# lightfun.net
KiCad netlist of a schematic drawn in EAGLE
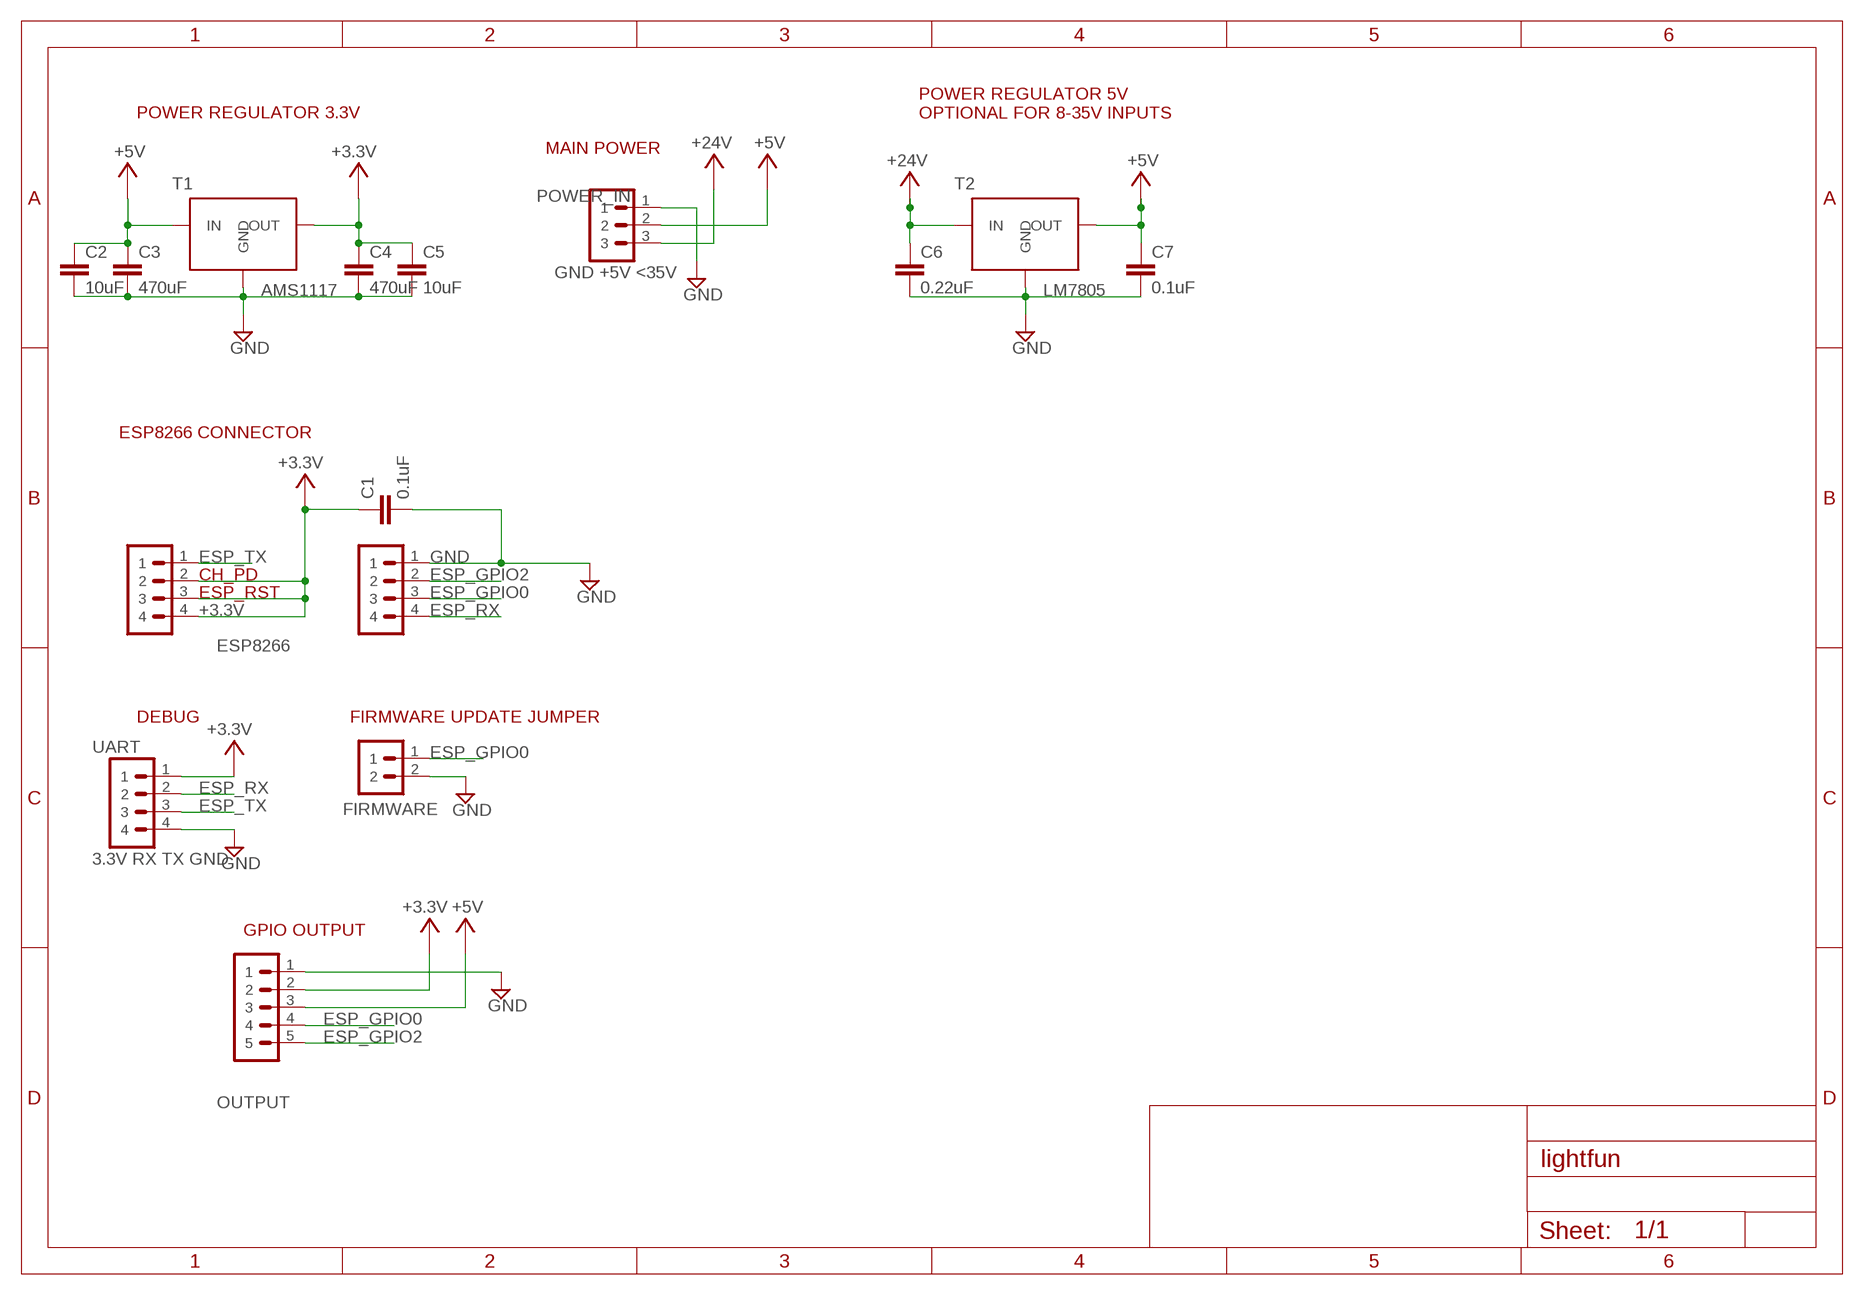
[diagram p0: schematic, sheet 1]

(export (version "E")
  (design (tool "Eeschema 10.0.6"))
  (components
    (comp (ref "C1")
      (value "0.1uF")
      (footprint "eagle-import:C2.5-2")
      (libsource (lib "eagle-import") (part "C2.5/2"))
    )
    (comp (ref "C2")
      (value "10uF")
      (footprint "eagle-import:C2.5-2")
      (libsource (lib "eagle-import") (part "C2.5/2"))
    )
    (comp (ref "C3")
      (value "470uF")
      (footprint "eagle-import:C2.5-2")
      (fields (field (name "MPN") "1C10Z5U104M050B"))
      (libsource (lib "eagle-import") (part "C2.5/2"))
    )
    (comp (ref "C4")
      (value "470uF")
      (footprint "eagle-import:C2.5-2")
      (fields (field (name "MPN") "FK18X5R0J106M"))
      (libsource (lib "eagle-import") (part "C2.5/2"))
    )
    (comp (ref "C5")
      (value "10uF")
      (footprint "eagle-import:C2.5-2")
      (libsource (lib "eagle-import") (part "C2.5/2"))
    )
    (comp (ref "C6")
      (value "0.22uF")
      (footprint "eagle-import:C2.5-2")
      (fields (field (name "MPN") "1C10Z5U104M050B"))
      (libsource (lib "eagle-import") (part "C2.5/2"))
    )
    (comp (ref "C7")
      (value "0.1uF")
      (footprint "eagle-import:C2.5-2")
      (fields (field (name "MPN") "FK18X5R0J106M"))
      (libsource (lib "eagle-import") (part "C2.5/2"))
    )
    (comp (ref "FIRMWARE")
      (value "FIRMWARE")
      (footprint "eagle-import:PIN-HEADER-2PIN")
      (libsource (lib "eagle-import") (part "PIN-HEADER-2PIN"))
    )
    (comp (ref "OUTPUT")
      (value "GND 3.3V 5V IO0 IO2")
      (footprint "eagle-import:PIN-HEADER-5PIN")
      (libsource (lib "eagle-import") (part "PIN-HEADER-5PIN"))
    )
    (comp (ref "P1")
      (value "ESP8266")
      (footprint "eagle-import:PIN-HEADER-4PIN")
      (libsource (lib "eagle-import") (part "PIN-HEADER-4PIN"))
    )
    (comp (ref "P2")
      (value "ESP8266 CONNECTOR")
      (footprint "eagle-import:PIN-HEADER-4PIN")
      (libsource (lib "eagle-import") (part "PIN-HEADER-4PIN"))
    )
    (comp (ref "POWER_IN")
      (value "GND +5V <35V")
      (footprint "eagle-import:PIN-HEADER-3PIN")
      (libsource (lib "eagle-import") (part "PIN-HEADER-3PIN"))
    )
    (comp (ref "T1")
      (value "AMS1117")
      (footprint "eagle-import:SOT-223")
      (fields (field (name "MPN") "LM2937ET-3.3"))
      (libsource (lib "eagle-import") (part "AMS1117"))
    )
    (comp (ref "T2")
      (value "LM7805")
      (footprint "eagle-import:TO-220")
      (fields (field (name "MPN") "LM2937ET-3.3"))
      (libsource (lib "eagle-import") (part "LM7805"))
    )
    (comp (ref "UART")
      (value "3.3V RX TX GND")
      (footprint "eagle-import:PIN-HEADER-4PIN")
      (libsource (lib "eagle-import") (part "PIN-HEADER-4PIN"))
    )
  )
  (nets
    (net (code "1") (name "+3.3V") (class "Default")
      (node (ref "C1") (pin "1") (pinfunction "1_1") (pintype "passive"))
      (node (ref "C4") (pin "1") (pinfunction "1_1") (pintype "passive"))
      (node (ref "C5") (pin "1") (pinfunction "1_1") (pintype "passive"))
      (node (ref "OUTPUT") (pin "2") (pinfunction "2_2") (pintype "passive"))
      (node (ref "P1") (pin "2") (pinfunction "2_2") (pintype "passive"))
      (node (ref "P1") (pin "3") (pinfunction "3_3") (pintype "passive"))
      (node (ref "P1") (pin "4") (pinfunction "4_4") (pintype "passive"))
      (node (ref "T1") (pin "2") (pinfunction "OUT_2") (pintype "power_in"))
      (node (ref "UART") (pin "1") (pinfunction "1_1") (pintype "passive"))
    )
    (net (code "2") (name "+5V") (class "Default")
      (node (ref "C2") (pin "1") (pinfunction "1_1") (pintype "passive"))
      (node (ref "C3") (pin "1") (pinfunction "1_1") (pintype "passive"))
      (node (ref "C7") (pin "1") (pinfunction "1_1") (pintype "passive"))
      (node (ref "OUTPUT") (pin "3") (pinfunction "3_3") (pintype "passive"))
      (node (ref "POWER_IN") (pin "2") (pinfunction "2_2") (pintype "passive"))
      (node (ref "T1") (pin "3") (pinfunction "IN_3") (pintype "power_in"))
      (node (ref "T2") (pin "OUTPUT") (pinfunction "OUT_OUTPUT") (pintype "power_in"))
    )
    (net (code "3") (name "+24V") (class "Default")
      (node (ref "C6") (pin "1") (pinfunction "1_1") (pintype "passive"))
      (node (ref "POWER_IN") (pin "3") (pinfunction "3_3") (pintype "passive"))
      (node (ref "T2") (pin "INPUT") (pinfunction "IN_INPUT") (pintype "power_in"))
    )
    (net (code "4") (name "/ESP_GPIO0") (class "Default")
      (node (ref "FIRMWARE") (pin "1") (pinfunction "1_1") (pintype "passive"))
      (node (ref "OUTPUT") (pin "4") (pinfunction "4_4") (pintype "passive"))
      (node (ref "P2") (pin "3") (pinfunction "3_3") (pintype "passive"))
    )
    (net (code "5") (name "/ESP_GPIO2") (class "Default")
      (node (ref "OUTPUT") (pin "5") (pinfunction "5_5") (pintype "passive"))
      (node (ref "P2") (pin "2") (pinfunction "2_2") (pintype "passive"))
    )
    (net (code "6") (name "/ESP_RX") (class "Default")
      (node (ref "P2") (pin "4") (pinfunction "4_4") (pintype "passive"))
      (node (ref "UART") (pin "2") (pinfunction "2_2") (pintype "passive"))
    )
    (net (code "7") (name "/ESP_TX") (class "Default")
      (node (ref "P1") (pin "1") (pinfunction "1_1") (pintype "passive"))
      (node (ref "UART") (pin "3") (pinfunction "3_3") (pintype "passive"))
    )
    (net (code "8") (name "GND") (class "Default")
      (node (ref "C1") (pin "2") (pinfunction "2_2") (pintype "passive"))
      (node (ref "C2") (pin "2") (pinfunction "2_2") (pintype "passive"))
      (node (ref "C3") (pin "2") (pinfunction "2_2") (pintype "passive"))
      (node (ref "C4") (pin "2") (pinfunction "2_2") (pintype "passive"))
      (node (ref "C5") (pin "2") (pinfunction "2_2") (pintype "passive"))
      (node (ref "C6") (pin "2") (pinfunction "2_2") (pintype "passive"))
      (node (ref "C7") (pin "2") (pinfunction "2_2") (pintype "passive"))
      (node (ref "FIRMWARE") (pin "2") (pinfunction "2_2") (pintype "passive"))
      (node (ref "OUTPUT") (pin "1") (pinfunction "1_1") (pintype "passive"))
      (node (ref "P2") (pin "1") (pinfunction "1_1") (pintype "passive"))
      (node (ref "POWER_IN") (pin "1") (pinfunction "1_1") (pintype "passive"))
      (node (ref "T1") (pin "1") (pinfunction "GND_1") (pintype "power_in"))
      (node (ref "T2") (pin "GND") (pinfunction "GND_GND") (pintype "power_in"))
      (node (ref "UART") (pin "4") (pinfunction "4_4") (pintype "passive"))
    )
  )
)
